# Sheet1.net
KiCad netlist of a schematic drawn in Altium Designer
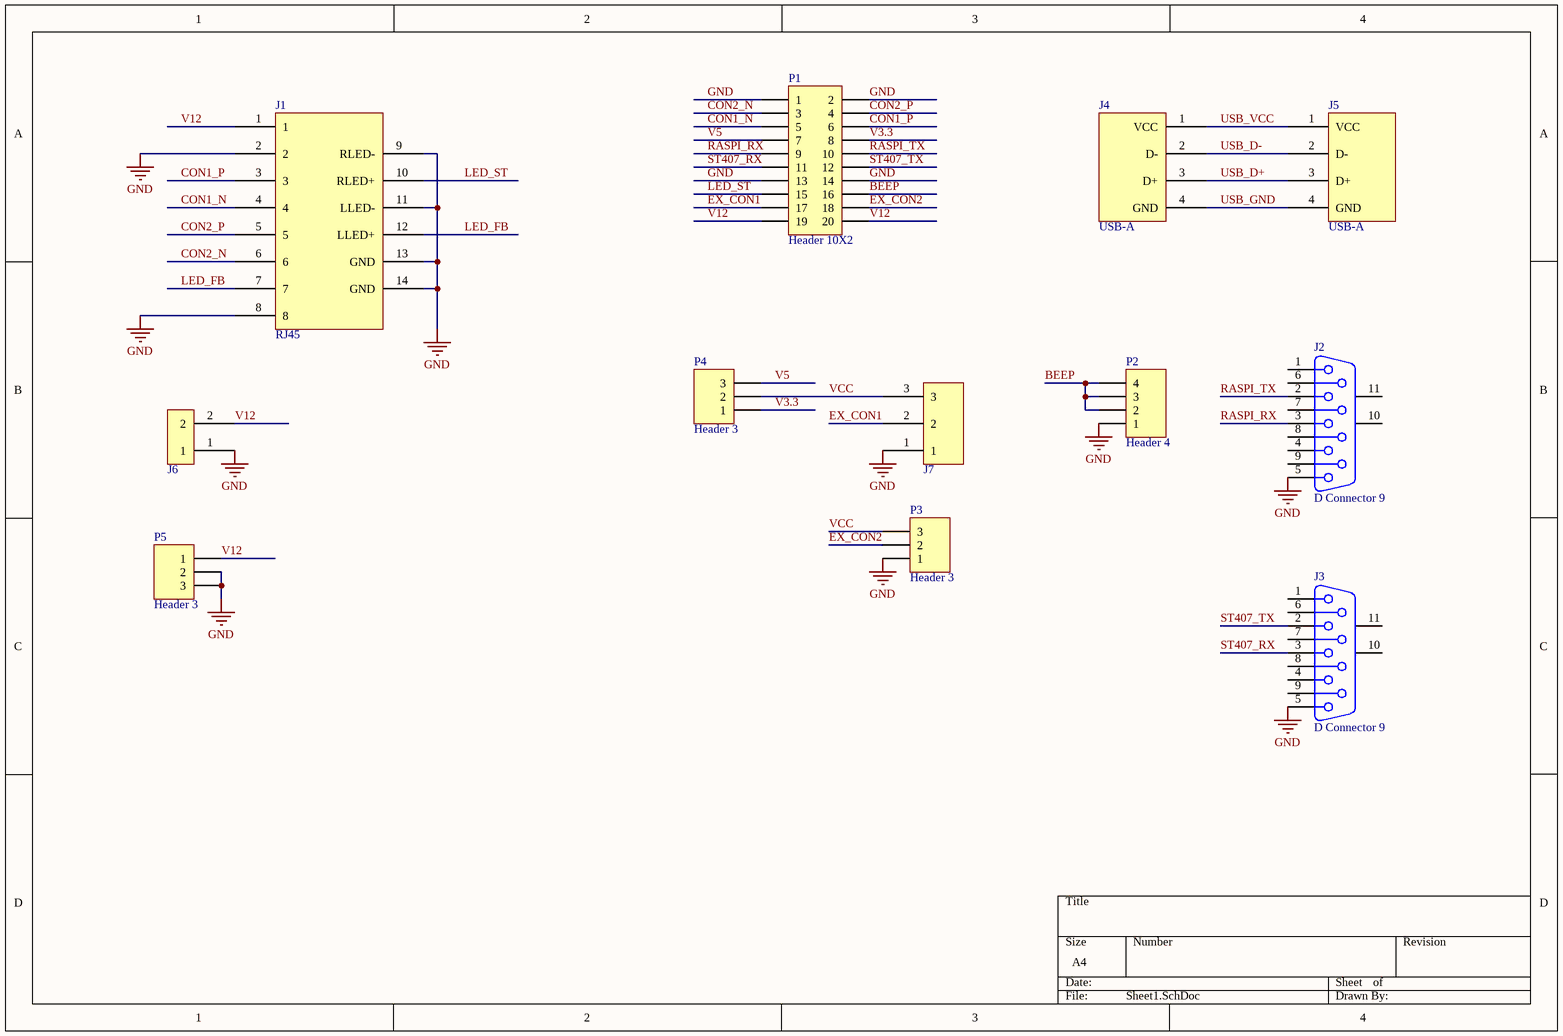
[diagram p0: Sheet1.SchDoc]

(export (version "E")
  (design (tool "Eeschema 10.0.6"))
  (components
    (comp (ref "J1") (value "RJ45") (footprint "RJ45_1") (libsource (lib "CHK-I") (part "RJ45_1")))
    (comp (ref "J2")
      (value "D Connector 9")
      (footprint "DSUB1.385-2H9")
      (description "Receptacle Assembly, 9 Position, Right Angle")
      (fields (field (name "PUBLISHER") "Altium Limited"))
      (libsource (lib "Miscellaneous Connectors") (part "D Connector 9"))
    )
    (comp (ref "J3")
      (value "D Connector 9")
      (footprint "DSUB1.385-2H9")
      (description "Receptacle Assembly, 9 Position, Right Angle")
      (fields (field (name "PUBLISHER") "Altium Limited"))
      (libsource (lib "Miscellaneous Connectors") (part "D Connector 9"))
    )
    (comp (ref "J4")
      (value "USB-A")
      (footprint "USB-A")
      (description "USB-A female")
      (libsource (lib "") (part "USB-A_1"))
    )
    (comp (ref "J5")
      (value "USB-A")
      (footprint "USB-A")
      (description "USB-A female")
      (libsource (lib "CHK-I") (part "USB-A"))
    )
    (comp (ref "J6") (value "XK7.62-2P") (footprint "XK7.62-2P") (libsource (lib "CHK-I") (part "XK7.62-2P")))
    (comp (ref "J7") (value "KF301-3P") (footprint "KF301-3P") (libsource (lib "CHK-I") (part "KF301-3P")))
    (comp (ref "P1")
      (value "Header 10X2")
      (footprint "HDR2X10")
      (description "Header, 10-Pin, Dual row")
      (fields (field (name "PUBLISHER") "Altium Limited"))
      (libsource (lib "Miscellaneous Connectors") (part "Header 10X2"))
    )
    (comp (ref "P2")
      (value "Header 4")
      (footprint "HDR1X4")
      (description "Header, 4-Pin")
      (fields (field (name "PUBLISHER") "Altium Limited"))
      (libsource (lib "Miscellaneous Connectors") (part "Header 4"))
    )
    (comp (ref "P3")
      (value "Header 3")
      (footprint "HDR1X3")
      (description "Header, 3-Pin")
      (fields (field (name "PUBLISHER") "Altium Limited"))
      (libsource (lib "") (part "Header 3_1"))
    )
    (comp (ref "P4")
      (value "Header 3")
      (footprint "HDR1X3")
      (description "Header, 3-Pin")
      (fields (field (name "PUBLISHER") "Altium Limited"))
      (libsource (lib "Miscellaneous Connectors") (part "Header 3"))
    )
    (comp (ref "P5")
      (value "Header 3")
      (footprint "DC005")
      (description "Header, 3-Pin")
      (fields (field (name "PUBLISHER") "Altium Limited"))
      (libsource (lib "") (part "Header 3_2"))
    )
  )
  (nets
    (net (code "1") (name "/BEEP") (class "Default")
      (node (ref "P1") (pin "16") (pinfunction "16_16") (pintype "passive"))
      (node (ref "P2") (pin "2") (pinfunction "2_2") (pintype "passive"))
      (node (ref "P2") (pin "3") (pinfunction "3_3") (pintype "passive"))
      (node (ref "P2") (pin "4") (pinfunction "4_4") (pintype "passive"))
    )
    (net (code "2") (name "/CON1_N") (class "Default")
      (node (ref "J1") (pin "4") (pinfunction "4_4") (pintype "passive"))
      (node (ref "P1") (pin "5") (pinfunction "5_5") (pintype "passive"))
    )
    (net (code "3") (name "/CON1_P") (class "Default")
      (node (ref "J1") (pin "3") (pinfunction "3_3") (pintype "passive"))
      (node (ref "P1") (pin "6") (pinfunction "6_6") (pintype "passive"))
    )
    (net (code "4") (name "/CON2_N") (class "Default")
      (node (ref "J1") (pin "6") (pinfunction "6_6") (pintype "passive"))
      (node (ref "P1") (pin "3") (pinfunction "3_3") (pintype "passive"))
    )
    (net (code "5") (name "/CON2_P") (class "Default")
      (node (ref "J1") (pin "5") (pinfunction "5_5") (pintype "passive"))
      (node (ref "P1") (pin "4") (pinfunction "4_4") (pintype "passive"))
    )
    (net (code "6") (name "/EX_CON1") (class "Default")
      (node (ref "J7") (pin "2") (pinfunction "2_2") (pintype "passive"))
      (node (ref "P1") (pin "17") (pinfunction "17_17") (pintype "passive"))
    )
    (net (code "7") (name "/EX_CON2") (class "Default")
      (node (ref "P1") (pin "18") (pinfunction "18_18") (pintype "passive"))
      (node (ref "P3") (pin "2") (pinfunction "2_2") (pintype "passive"))
    )
    (net (code "8") (name "/LED_FB") (class "Default")
      (node (ref "J1") (pin "12") (pinfunction "LLED+_12") (pintype "passive"))
      (node (ref "J1") (pin "7") (pinfunction "7_7") (pintype "passive"))
    )
    (net (code "9") (name "/LED_ST") (class "Default")
      (node (ref "J1") (pin "10") (pinfunction "RLED+_10") (pintype "passive"))
      (node (ref "P1") (pin "15") (pinfunction "15_15") (pintype "passive"))
    )
    (net (code "10") (name "/RASPI_RX") (class "Default")
      (node (ref "J2") (pin "3") (pinfunction "3_3") (pintype "passive"))
      (node (ref "P1") (pin "9") (pinfunction "9_9") (pintype "passive"))
    )
    (net (code "11") (name "/RASPI_TX") (class "Default")
      (node (ref "J2") (pin "2") (pinfunction "2_2") (pintype "passive"))
      (node (ref "P1") (pin "10") (pinfunction "10_10") (pintype "passive"))
    )
    (net (code "12") (name "/ST407_RX") (class "Default")
      (node (ref "J3") (pin "3") (pinfunction "3_3") (pintype "passive"))
      (node (ref "P1") (pin "11") (pinfunction "11_11") (pintype "passive"))
    )
    (net (code "13") (name "/ST407_TX") (class "Default")
      (node (ref "J3") (pin "2") (pinfunction "2_2") (pintype "passive"))
      (node (ref "P1") (pin "12") (pinfunction "12_12") (pintype "passive"))
    )
    (net (code "14") (name "/USB_D+") (class "Default")
      (node (ref "J4") (pin "3") (pinfunction "D+_3") (pintype "passive"))
      (node (ref "J5") (pin "3") (pinfunction "D+_3") (pintype "passive"))
    )
    (net (code "15") (name "/USB_D-") (class "Default")
      (node (ref "J4") (pin "2") (pinfunction "D-_2") (pintype "passive"))
      (node (ref "J5") (pin "2") (pinfunction "D-_2") (pintype "passive"))
    )
    (net (code "16") (name "/USB_GND") (class "Default")
      (node (ref "J4") (pin "4") (pinfunction "GND_4") (pintype "passive"))
      (node (ref "J5") (pin "4") (pinfunction "GND_4") (pintype "passive"))
    )
    (net (code "17") (name "/USB_VCC") (class "Default")
      (node (ref "J4") (pin "1") (pinfunction "VCC_1") (pintype "passive"))
      (node (ref "J5") (pin "1") (pinfunction "VCC_1") (pintype "passive"))
    )
    (net (code "18") (name "/V3.3") (class "Default")
      (node (ref "P1") (pin "8") (pinfunction "8_8") (pintype "passive"))
      (node (ref "P4") (pin "1") (pinfunction "1_1") (pintype "passive"))
    )
    (net (code "19") (name "/V5") (class "Default")
      (node (ref "P1") (pin "7") (pinfunction "7_7") (pintype "passive"))
      (node (ref "P4") (pin "3") (pinfunction "3_3") (pintype "passive"))
    )
    (net (code "20") (name "/V12") (class "Default")
      (node (ref "J1") (pin "1") (pinfunction "1_1") (pintype "passive"))
      (node (ref "J6") (pin "2") (pinfunction "2_2") (pintype "passive"))
      (node (ref "P1") (pin "19") (pinfunction "19_19") (pintype "passive"))
      (node (ref "P1") (pin "20") (pinfunction "20_20") (pintype "passive"))
      (node (ref "P5") (pin "1") (pinfunction "1_1") (pintype "passive"))
    )
    (net (code "21") (name "/VCC") (class "Default")
      (node (ref "J7") (pin "3") (pinfunction "3_3") (pintype "passive"))
      (node (ref "P3") (pin "3") (pinfunction "3_3") (pintype "passive"))
      (node (ref "P4") (pin "2") (pinfunction "2_2") (pintype "passive"))
    )
    (net (code "22") (name "GND") (class "Default")
      (node (ref "J1") (pin "11") (pinfunction "LLED-_11") (pintype "passive"))
      (node (ref "J1") (pin "13") (pinfunction "GND_13") (pintype "passive"))
      (node (ref "J1") (pin "14") (pinfunction "GND_14") (pintype "passive"))
      (node (ref "J1") (pin "2") (pinfunction "2_2") (pintype "passive"))
      (node (ref "J1") (pin "8") (pinfunction "8_8") (pintype "passive"))
      (node (ref "J1") (pin "9") (pinfunction "RLED-_9") (pintype "passive"))
      (node (ref "J2") (pin "5") (pinfunction "5_5") (pintype "passive"))
      (node (ref "J3") (pin "5") (pinfunction "5_5") (pintype "passive"))
      (node (ref "J6") (pin "1") (pinfunction "1_1") (pintype "passive"))
      (node (ref "J7") (pin "1") (pinfunction "1_1") (pintype "passive"))
      (node (ref "P1") (pin "1") (pinfunction "1_1") (pintype "passive"))
      (node (ref "P1") (pin "13") (pinfunction "13_13") (pintype "passive"))
      (node (ref "P1") (pin "14") (pinfunction "14_14") (pintype "passive"))
      (node (ref "P1") (pin "2") (pinfunction "2_2") (pintype "passive"))
      (node (ref "P2") (pin "1") (pinfunction "1_1") (pintype "passive"))
      (node (ref "P3") (pin "1") (pinfunction "1_1") (pintype "passive"))
      (node (ref "P5") (pin "2") (pinfunction "2_2") (pintype "passive"))
      (node (ref "P5") (pin "3") (pinfunction "3_3") (pintype "passive"))
    )
    (net (code "23") (name "unconnected-(J2-MH1-Pad10)") (class "Default")
      (node (ref "J2") (pin "10") (pinfunction "MH1_10") (pintype "passive"))
    )
    (net (code "24") (name "unconnected-(J2-MH2-Pad11)") (class "Default")
      (node (ref "J2") (pin "11") (pinfunction "MH2_11") (pintype "passive"))
    )
    (net (code "25") (name "unconnected-(J2-Pad1)") (class "Default")
      (node (ref "J2") (pin "1") (pinfunction "1_1") (pintype "passive"))
    )
    (net (code "26") (name "unconnected-(J2-Pad4)") (class "Default")
      (node (ref "J2") (pin "4") (pinfunction "4_4") (pintype "passive"))
    )
    (net (code "27") (name "unconnected-(J2-Pad6)") (class "Default")
      (node (ref "J2") (pin "6") (pinfunction "6_6") (pintype "passive"))
    )
    (net (code "28") (name "unconnected-(J2-Pad7)") (class "Default")
      (node (ref "J2") (pin "7") (pinfunction "7_7") (pintype "passive"))
    )
    (net (code "29") (name "unconnected-(J2-Pad8)") (class "Default")
      (node (ref "J2") (pin "8") (pinfunction "8_8") (pintype "passive"))
    )
    (net (code "30") (name "unconnected-(J2-Pad9)") (class "Default")
      (node (ref "J2") (pin "9") (pinfunction "9_9") (pintype "passive"))
    )
    (net (code "31") (name "unconnected-(J3-MH1-Pad10)") (class "Default")
      (node (ref "J3") (pin "10") (pinfunction "MH1_10") (pintype "passive"))
    )
    (net (code "32") (name "unconnected-(J3-MH2-Pad11)") (class "Default")
      (node (ref "J3") (pin "11") (pinfunction "MH2_11") (pintype "passive"))
    )
    (net (code "33") (name "unconnected-(J3-Pad1)") (class "Default")
      (node (ref "J3") (pin "1") (pinfunction "1_1") (pintype "passive"))
    )
    (net (code "34") (name "unconnected-(J3-Pad4)") (class "Default")
      (node (ref "J3") (pin "4") (pinfunction "4_4") (pintype "passive"))
    )
    (net (code "35") (name "unconnected-(J3-Pad6)") (class "Default")
      (node (ref "J3") (pin "6") (pinfunction "6_6") (pintype "passive"))
    )
    (net (code "36") (name "unconnected-(J3-Pad7)") (class "Default")
      (node (ref "J3") (pin "7") (pinfunction "7_7") (pintype "passive"))
    )
    (net (code "37") (name "unconnected-(J3-Pad8)") (class "Default")
      (node (ref "J3") (pin "8") (pinfunction "8_8") (pintype "passive"))
    )
    (net (code "38") (name "unconnected-(J3-Pad9)") (class "Default")
      (node (ref "J3") (pin "9") (pinfunction "9_9") (pintype "passive"))
    )
  )
)
